# Genesis_Model2_RGB_LED.net
KiCad netlist of a schematic drawn in EAGLE
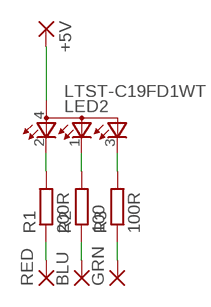
[diagram p0: schematic, sheet 1]

(export (version "E")
  (design (tool "Eeschema 10.0.6"))
  (components
    (comp (ref "+5V")
      (value "SMD2TOP")
      (footprint "eagle-import:SMD_SOIC")
      (libsource (lib "eagle-import") (part "SMD2TOP"))
    )
    (comp (ref "BLU")
      (value "SMD2TOP")
      (footprint "eagle-import:SMD_SOIC")
      (libsource (lib "eagle-import") (part "SMD2TOP"))
    )
    (comp (ref "GRN")
      (value "SMD2TOP")
      (footprint "eagle-import:SMD_SOIC")
      (libsource (lib "eagle-import") (part "SMD2TOP"))
    )
    (comp (ref "LED2")
      (value "LTST-C19FD1WT")
      (footprint "eagle-import:LTST-C19FD1WT")
      (libsource (lib "eagle-import") (part "LTST-C19FD1WT"))
    )
    (comp (ref "R1")
      (value "200R")
      (footprint "eagle-import:R0805")
      (libsource (lib "eagle-import") (part "R-EU_R0805"))
    )
    (comp (ref "R2")
      (value "100")
      (footprint "eagle-import:R0805")
      (libsource (lib "eagle-import") (part "R-EU_R0805"))
    )
    (comp (ref "R3")
      (value "100R")
      (footprint "eagle-import:R0805")
      (libsource (lib "eagle-import") (part "R-EU_R0805"))
    )
    (comp (ref "RED")
      (value "SMD2TOP")
      (footprint "eagle-import:SMD_SOIC")
      (libsource (lib "eagle-import") (part "SMD2TOP"))
    )
  )
  (nets
    (net (code "1") (name "Net-(+5V-P)") (class "Default")
      (node (ref "+5V") (pin "1") (pinfunction "P_1") (pintype "passive"))
      (node (ref "LED2") (pin "4") (pinfunction "A_4") (pintype "passive"))
    )
    (net (code "2") (name "Net-(BLU-P)") (class "Default")
      (node (ref "BLU") (pin "1") (pinfunction "P_1") (pintype "passive"))
      (node (ref "R2") (pin "1") (pinfunction "1_1") (pintype "passive"))
    )
    (net (code "3") (name "Net-(GRN-P)") (class "Default")
      (node (ref "GRN") (pin "1") (pinfunction "P_1") (pintype "passive"))
      (node (ref "R3") (pin "1") (pinfunction "1_1") (pintype "passive"))
    )
    (net (code "4") (name "Net-(LED2-CBLUE)") (class "Default")
      (node (ref "LED2") (pin "1") (pinfunction "CBLUE_1") (pintype "passive"))
      (node (ref "R2") (pin "2") (pinfunction "2_2") (pintype "passive"))
    )
    (net (code "5") (name "Net-(LED2-CGREEN)") (class "Default")
      (node (ref "LED2") (pin "3") (pinfunction "CGREEN_3") (pintype "passive"))
      (node (ref "R3") (pin "2") (pinfunction "2_2") (pintype "passive"))
    )
    (net (code "6") (name "Net-(LED2-CRED)") (class "Default")
      (node (ref "LED2") (pin "2") (pinfunction "CRED_2") (pintype "passive"))
      (node (ref "R1") (pin "2") (pinfunction "2_2") (pintype "passive"))
    )
    (net (code "7") (name "Net-(RED-P)") (class "Default")
      (node (ref "R1") (pin "1") (pinfunction "1_1") (pintype "passive"))
      (node (ref "RED") (pin "1") (pinfunction "P_1") (pintype "passive"))
    )
  )
)
